# Sensors.net
KiCad netlist of a schematic drawn in Altium Designer
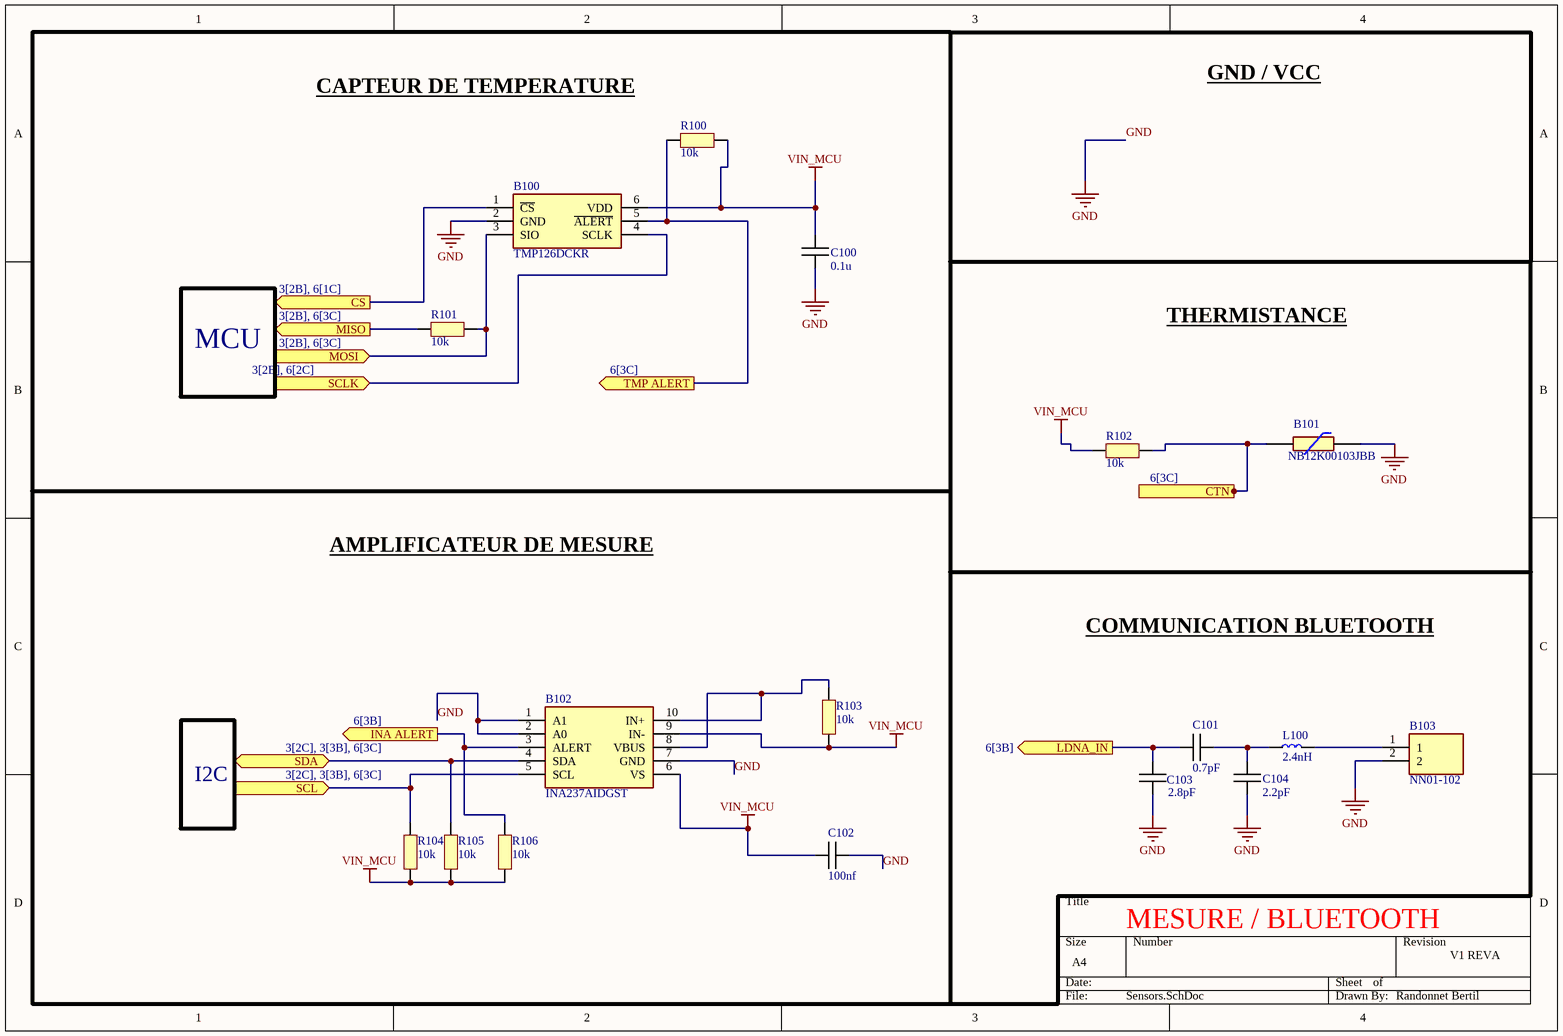
[diagram p0: Sensors.SchDoc]

(export (version "E")
  (design (tool "Eeschema 10.0.6"))
  (components
    (comp (ref "B100")
      (value "TMP126DCKR")
      (footprint "SOT65P210X110-6N")
      (fields (field (name "MOUSER PART NUMBER") "595-TMP126DCKR"))
      (libsource (lib "SCHLibrary") (part "TMP126DCKR"))
    )
    (comp (ref "B101")
      (value "NB12K00103JBB")
      (footprint "RESC2212X50N")
      (description "NTC SMD Thermistor, NB12K, 10K, 5% AVX 10k 0805 Protection NTC Thermistor, 5s, 2 x 1.25 x 1.3mm")
      (fields (field (name "MOUSER PART NUMBER") "581-NB12K00103JBB"))
      (libsource (lib "SCHLibrary") (part "NB12K00103JBB"))
    )
    (comp (ref "B102")
      (value "INA237AIDGST")
      (footprint "SOP50P490X110-10N")
      (fields (field (name "MOUSER PART NUMBER") "595-INA237AIDGST"))
      (libsource (lib "SCHLibrary") (part "INA237AIDGST"))
    )
    (comp (ref "B103")
      (value "NN01-102")
      (footprint "NN01-102")
      (description "Antennes Compact Reach Xtend 2.4 GHz")
      (libsource (lib "SCHLibrary") (part "NN01-102"))
    )
    (comp (ref "C100")
      (value "0.1u")
      (footprint "CAPC1005X06N")
      (libsource (lib "SCHLibrary") (part "Capacitor"))
    )
    (comp (ref "C101")
      (value "0.7pF")
      (footprint "CAPC1005X06N")
      (libsource (lib "SCHLibrary") (part "Capacitor"))
    )
    (comp (ref "C102")
      (value "100nf")
      (footprint "CAPC1005X06N")
      (libsource (lib "SCHLibrary") (part "Capacitor"))
    )
    (comp (ref "C103")
      (value "2.8pF")
      (footprint "CAPC1005X06N")
      (libsource (lib "SCHLibrary") (part "Capacitor"))
    )
    (comp (ref "C104")
      (value "2.2pF")
      (footprint "CAPC1005X06N")
      (libsource (lib "SCHLibrary") (part "Capacitor"))
    )
    (comp (ref "L100")
      (value "2.4nH")
      (footprint "LQPC1005X06N")
      (libsource (lib "SCHLibrary") (part "Bobine"))
    )
    (comp (ref "R100") (value "10k") (footprint "RESC1005X06N") (libsource (lib "") (part "Resistor_1")))
    (comp (ref "R101") (value "10k") (footprint "RESC1005X06N") (libsource (lib "") (part "Resistor_1")))
    (comp (ref "R102") (value "10k") (footprint "RESC1005X06N") (libsource (lib "") (part "Resistor_1")))
    (comp (ref "R103")
      (value "10k")
      (footprint "RESC1005X06N")
      (libsource (lib "SCHLibrary") (part "Resistor"))
    )
    (comp (ref "R104")
      (value "10k")
      (footprint "RESC1005X06N")
      (libsource (lib "SCHLibrary") (part "Resistor"))
    )
    (comp (ref "R105")
      (value "10k")
      (footprint "RESC1005X06N")
      (libsource (lib "SCHLibrary") (part "Resistor"))
    )
    (comp (ref "R106")
      (value "10k")
      (footprint "RESC1005X06N")
      (libsource (lib "SCHLibrary") (part "Resistor"))
    )
  )
  (nets
    (net (code "1") (name "/CS") (class "Default")
      (node (ref "B100") (pin "1") (pinfunction "~{CS}_1") (pintype "passive"))
    )
    (net (code "2") (name "/CTN") (class "Default")
      (node (ref "B101") (pin "2") (pinfunction "2_2") (pintype "passive"))
      (node (ref "R102") (pin "2") (pinfunction "2_2") (pintype "passive"))
    )
    (net (code "3") (name "/INA ALERT") (class "Default")
      (node (ref "B102") (pin "3") (pinfunction "ALERT_3") (pintype "passive"))
      (node (ref "R106") (pin "2") (pinfunction "2_2") (pintype "passive"))
    )
    (net (code "4") (name "/LDNA_IN") (class "Default")
      (node (ref "C101") (pin "1") (pinfunction "1_1") (pintype "passive"))
      (node (ref "C103") (pin "1") (pinfunction "1_1") (pintype "passive"))
    )
    (net (code "5") (name "/MISO") (class "Default")
      (node (ref "R101") (pin "1") (pinfunction "1_1") (pintype "passive"))
    )
    (net (code "6") (name "/MOSI") (class "Default")
      (node (ref "B100") (pin "3") (pinfunction "SIO_3") (pintype "passive"))
      (node (ref "R101") (pin "2") (pinfunction "2_2") (pintype "passive"))
    )
    (net (code "7") (name "/SCL") (class "Default")
      (node (ref "B102") (pin "5") (pinfunction "SCL_5") (pintype "passive"))
      (node (ref "R104") (pin "2") (pinfunction "2_2") (pintype "passive"))
    )
    (net (code "8") (name "/SCLK") (class "Default")
      (node (ref "B100") (pin "4") (pinfunction "SCLK_4") (pintype "passive"))
    )
    (net (code "9") (name "/SDA") (class "Default")
      (node (ref "B102") (pin "4") (pinfunction "SDA_4") (pintype "passive"))
      (node (ref "R105") (pin "2") (pinfunction "2_2") (pintype "passive"))
    )
    (net (code "10") (name "/TMP ALERT") (class "Default")
      (node (ref "B100") (pin "5") (pinfunction "~{ALERT}_5") (pintype "passive"))
      (node (ref "R100") (pin "1") (pinfunction "1_1") (pintype "passive"))
    )
    (net (code "11") (name "GND") (class "Default")
      (node (ref "B100") (pin "2") (pinfunction "GND_2") (pintype "passive"))
      (node (ref "B101") (pin "1") (pinfunction "1_1") (pintype "passive"))
      (node (ref "B102") (pin "1") (pinfunction "A1_1") (pintype "passive"))
      (node (ref "B102") (pin "2") (pinfunction "A0_2") (pintype "passive"))
      (node (ref "B102") (pin "7") (pinfunction "GND_7") (pintype "passive"))
      (node (ref "B103") (pin "2") (pinfunction "2_2") (pintype "passive"))
      (node (ref "C100") (pin "2") (pinfunction "2_2") (pintype "passive"))
      (node (ref "C102") (pin "1") (pinfunction "1_1") (pintype "passive"))
      (node (ref "C103") (pin "2") (pinfunction "2_2") (pintype "passive"))
      (node (ref "C104") (pin "2") (pinfunction "2_2") (pintype "passive"))
    )
    (net (code "12") (name "Net-(B102-IN+)") (class "Default")
      (node (ref "B102") (pin "10") (pinfunction "IN+_10") (pintype "passive"))
      (node (ref "B102") (pin "8") (pinfunction "VBUS_8") (pintype "passive"))
      (node (ref "R103") (pin "2") (pinfunction "2_2") (pintype "passive"))
    )
    (net (code "13") (name "Net-(B103-Pad1)") (class "Default")
      (node (ref "B103") (pin "1") (pinfunction "1_1") (pintype "passive"))
      (node (ref "L100") (pin "2") (pinfunction "2_2") (pintype "passive"))
    )
    (net (code "14") (name "Net-(C101-Pad2)") (class "Default")
      (node (ref "C101") (pin "2") (pinfunction "2_2") (pintype "passive"))
      (node (ref "C104") (pin "1") (pinfunction "1_1") (pintype "passive"))
      (node (ref "L100") (pin "1") (pinfunction "1_1") (pintype "passive"))
    )
    (net (code "15") (name "VIN_MCU") (class "Default")
      (node (ref "B100") (pin "6") (pinfunction "VDD_6") (pintype "passive"))
      (node (ref "B102") (pin "6") (pinfunction "VS_6") (pintype "passive"))
      (node (ref "B102") (pin "9") (pinfunction "IN-_9") (pintype "passive"))
      (node (ref "C100") (pin "1") (pinfunction "1_1") (pintype "passive"))
      (node (ref "C102") (pin "2") (pinfunction "2_2") (pintype "passive"))
      (node (ref "R100") (pin "2") (pinfunction "2_2") (pintype "passive"))
      (node (ref "R102") (pin "1") (pinfunction "1_1") (pintype "passive"))
      (node (ref "R103") (pin "1") (pinfunction "1_1") (pintype "passive"))
      (node (ref "R104") (pin "1") (pinfunction "1_1") (pintype "passive"))
      (node (ref "R105") (pin "1") (pinfunction "1_1") (pintype "passive"))
      (node (ref "R106") (pin "1") (pinfunction "1_1") (pintype "passive"))
    )
  )
)
